# Audio.net
KiCad netlist of a schematic drawn in Altium Designer
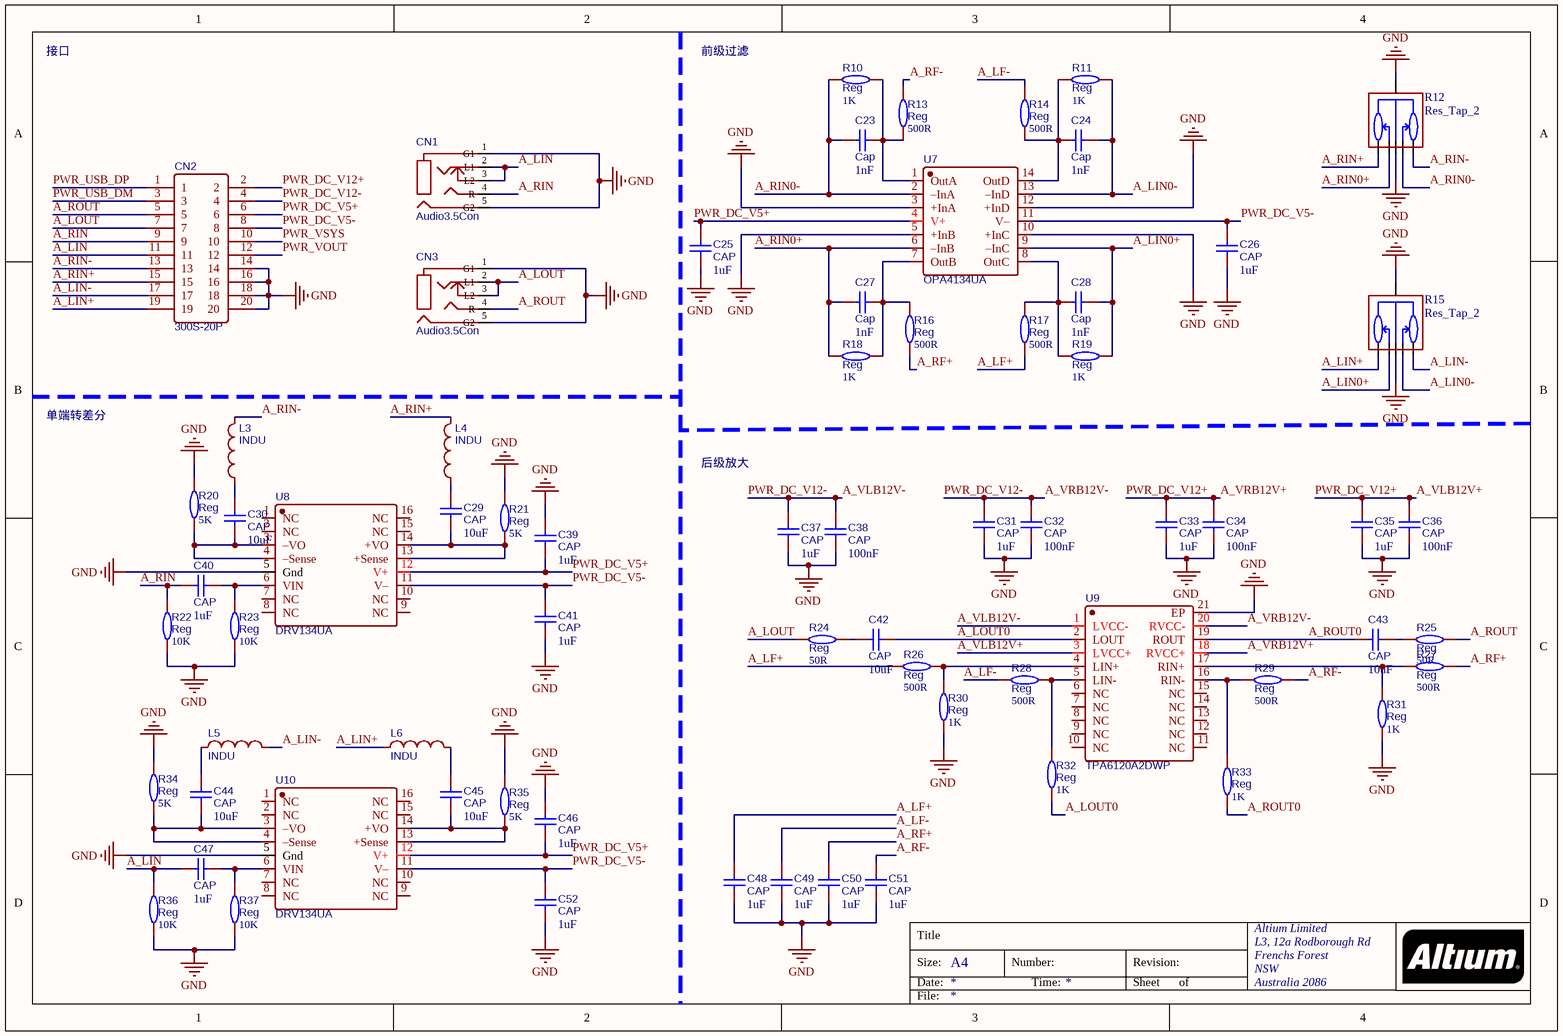
[diagram p0: Audio.SchDoc]

(export (version "E")
  (design (tool "Eeschema 10.0.6"))
  (components
    (comp (ref "C23")
      (value "Cap")
      (footprint "C0603")
      (fields
        (field (name "BOM_SUPPLIER PART") "C302008")
        (field (name "BOM_MANUFACTURER PART") "0603B103K101CT")
        (field (name "ALTIUM_VALUE") "1nF")
        (field (name "CONTRIBUTOR") "LCSC")
      )
      (libsource (lib "Levent_lib") (part "CAP"))
    )
    (comp (ref "C24")
      (value "Cap")
      (footprint "C0603")
      (fields
        (field (name "BOM_SUPPLIER PART") "C302008")
        (field (name "BOM_MANUFACTURER PART") "0603B103K101CT")
        (field (name "ALTIUM_VALUE") "1nF")
        (field (name "CONTRIBUTOR") "LCSC")
      )
      (libsource (lib "Levent_lib") (part "CAP"))
    )
    (comp (ref "C25")
      (value "CAP")
      (footprint "C0603")
      (description "Cap")
      (fields
        (field (name "BOM_SUPPLIER PART") "C302008")
        (field (name "BOM_MANUFACTURER PART") "0603B103K101CT")
        (field (name "ALTIUM_VALUE") "1uF")
        (field (name "CONTRIBUTOR") "LCSC")
      )
      (libsource (lib "Levent_lib") (part "CAP"))
    )
    (comp (ref "C26")
      (value "CAP")
      (footprint "C0603")
      (description "Cap")
      (fields
        (field (name "BOM_SUPPLIER PART") "C302008")
        (field (name "BOM_MANUFACTURER PART") "0603B103K101CT")
        (field (name "ALTIUM_VALUE") "1uF")
        (field (name "CONTRIBUTOR") "LCSC")
      )
      (libsource (lib "Levent_lib") (part "CAP"))
    )
    (comp (ref "C27")
      (value "Cap")
      (footprint "C0603")
      (fields
        (field (name "BOM_SUPPLIER PART") "C302008")
        (field (name "BOM_MANUFACTURER PART") "0603B103K101CT")
        (field (name "ALTIUM_VALUE") "1nF")
        (field (name "CONTRIBUTOR") "LCSC")
      )
      (libsource (lib "Levent_lib") (part "CAP"))
    )
    (comp (ref "C28")
      (value "Cap")
      (footprint "C0603")
      (fields
        (field (name "BOM_SUPPLIER PART") "C302008")
        (field (name "BOM_MANUFACTURER PART") "0603B103K101CT")
        (field (name "ALTIUM_VALUE") "1nF")
        (field (name "CONTRIBUTOR") "LCSC")
      )
      (libsource (lib "Levent_lib") (part "CAP"))
    )
    (comp (ref "C29")
      (value "CAP")
      (footprint "C0603")
      (description "Cap")
      (fields
        (field (name "BOM_SUPPLIER PART") "C302008")
        (field (name "BOM_MANUFACTURER PART") "0603B103K101CT")
        (field (name "ALTIUM_VALUE") "10uF")
        (field (name "CONTRIBUTOR") "LCSC")
      )
      (libsource (lib "Levent_lib") (part "CAP"))
    )
    (comp (ref "C30")
      (value "CAP")
      (footprint "C0603")
      (description "Cap")
      (fields
        (field (name "BOM_SUPPLIER PART") "C302008")
        (field (name "BOM_MANUFACTURER PART") "0603B103K101CT")
        (field (name "ALTIUM_VALUE") "10uF")
        (field (name "CONTRIBUTOR") "LCSC")
      )
      (libsource (lib "Levent_lib") (part "CAP"))
    )
    (comp (ref "C31")
      (value "CAP")
      (footprint "C0603")
      (description "Cap")
      (fields
        (field (name "BOM_SUPPLIER PART") "C302008")
        (field (name "BOM_MANUFACTURER PART") "0603B103K101CT")
        (field (name "ALTIUM_VALUE") "1uF")
        (field (name "CONTRIBUTOR") "LCSC")
      )
      (libsource (lib "Levent_lib") (part "CAP"))
    )
    (comp (ref "C32")
      (value "CAP")
      (footprint "C0603")
      (description "Cap")
      (fields
        (field (name "BOM_SUPPLIER PART") "C302008")
        (field (name "BOM_MANUFACTURER PART") "0603B103K101CT")
        (field (name "ALTIUM_VALUE") "100nF")
        (field (name "CONTRIBUTOR") "LCSC")
      )
      (libsource (lib "Levent_lib") (part "CAP"))
    )
    (comp (ref "C33")
      (value "CAP")
      (footprint "C0603")
      (description "Cap")
      (fields
        (field (name "BOM_SUPPLIER PART") "C302008")
        (field (name "BOM_MANUFACTURER PART") "0603B103K101CT")
        (field (name "ALTIUM_VALUE") "1uF")
        (field (name "CONTRIBUTOR") "LCSC")
      )
      (libsource (lib "Levent_lib") (part "CAP"))
    )
    (comp (ref "C34")
      (value "CAP")
      (footprint "C0603")
      (description "Cap")
      (fields
        (field (name "BOM_SUPPLIER PART") "C302008")
        (field (name "BOM_MANUFACTURER PART") "0603B103K101CT")
        (field (name "ALTIUM_VALUE") "100nF")
        (field (name "CONTRIBUTOR") "LCSC")
      )
      (libsource (lib "Levent_lib") (part "CAP"))
    )
    (comp (ref "C35")
      (value "CAP")
      (footprint "C0603")
      (description "Cap")
      (fields
        (field (name "BOM_SUPPLIER PART") "C302008")
        (field (name "BOM_MANUFACTURER PART") "0603B103K101CT")
        (field (name "ALTIUM_VALUE") "1uF")
        (field (name "CONTRIBUTOR") "LCSC")
      )
      (libsource (lib "Levent_lib") (part "CAP"))
    )
    (comp (ref "C36")
      (value "CAP")
      (footprint "C0603")
      (description "Cap")
      (fields
        (field (name "BOM_SUPPLIER PART") "C302008")
        (field (name "BOM_MANUFACTURER PART") "0603B103K101CT")
        (field (name "ALTIUM_VALUE") "100nF")
        (field (name "CONTRIBUTOR") "LCSC")
      )
      (libsource (lib "Levent_lib") (part "CAP"))
    )
    (comp (ref "C37")
      (value "CAP")
      (footprint "C0603")
      (description "Cap")
      (fields
        (field (name "BOM_SUPPLIER PART") "C302008")
        (field (name "BOM_MANUFACTURER PART") "0603B103K101CT")
        (field (name "ALTIUM_VALUE") "1uF")
        (field (name "CONTRIBUTOR") "LCSC")
      )
      (libsource (lib "Levent_lib") (part "CAP"))
    )
    (comp (ref "C38")
      (value "CAP")
      (footprint "C0603")
      (description "Cap")
      (fields
        (field (name "BOM_SUPPLIER PART") "C302008")
        (field (name "BOM_MANUFACTURER PART") "0603B103K101CT")
        (field (name "ALTIUM_VALUE") "100nF")
        (field (name "CONTRIBUTOR") "LCSC")
      )
      (libsource (lib "Levent_lib") (part "CAP"))
    )
    (comp (ref "C39")
      (value "CAP")
      (footprint "C0603")
      (description "Cap")
      (fields
        (field (name "BOM_SUPPLIER PART") "C302008")
        (field (name "BOM_MANUFACTURER PART") "0603B103K101CT")
        (field (name "ALTIUM_VALUE") "1uF")
        (field (name "CONTRIBUTOR") "LCSC")
      )
      (libsource (lib "Levent_lib") (part "CAP"))
    )
    (comp (ref "C40")
      (value "CAP")
      (footprint "C0603")
      (description "Cap")
      (fields
        (field (name "BOM_SUPPLIER PART") "C302008")
        (field (name "BOM_MANUFACTURER PART") "0603B103K101CT")
        (field (name "ALTIUM_VALUE") "1uF")
        (field (name "CONTRIBUTOR") "LCSC")
      )
      (libsource (lib "Levent_lib") (part "CAP"))
    )
    (comp (ref "C41")
      (value "CAP")
      (footprint "C0603")
      (description "Cap")
      (fields
        (field (name "BOM_SUPPLIER PART") "C302008")
        (field (name "BOM_MANUFACTURER PART") "0603B103K101CT")
        (field (name "ALTIUM_VALUE") "1uF")
        (field (name "CONTRIBUTOR") "LCSC")
      )
      (libsource (lib "Levent_lib") (part "CAP"))
    )
    (comp (ref "C42")
      (value "CAP")
      (footprint "C0603")
      (description "Cap")
      (fields
        (field (name "BOM_SUPPLIER PART") "C302008")
        (field (name "BOM_MANUFACTURER PART") "0603B103K101CT")
        (field (name "ALTIUM_VALUE") "10uF")
        (field (name "CONTRIBUTOR") "LCSC")
      )
      (libsource (lib "Levent_lib") (part "CAP"))
    )
    (comp (ref "C43")
      (value "CAP")
      (footprint "C0603")
      (description "Cap")
      (fields
        (field (name "BOM_SUPPLIER PART") "C302008")
        (field (name "BOM_MANUFACTURER PART") "0603B103K101CT")
        (field (name "ALTIUM_VALUE") "10uF")
        (field (name "CONTRIBUTOR") "LCSC")
      )
      (libsource (lib "Levent_lib") (part "CAP"))
    )
    (comp (ref "C44")
      (value "CAP")
      (footprint "C0603")
      (description "Cap")
      (fields
        (field (name "BOM_SUPPLIER PART") "C302008")
        (field (name "BOM_MANUFACTURER PART") "0603B103K101CT")
        (field (name "ALTIUM_VALUE") "10uF")
        (field (name "CONTRIBUTOR") "LCSC")
      )
      (libsource (lib "Levent_lib") (part "CAP"))
    )
    (comp (ref "C45")
      (value "CAP")
      (footprint "C0603")
      (description "Cap")
      (fields
        (field (name "BOM_SUPPLIER PART") "C302008")
        (field (name "BOM_MANUFACTURER PART") "0603B103K101CT")
        (field (name "ALTIUM_VALUE") "10uF")
        (field (name "CONTRIBUTOR") "LCSC")
      )
      (libsource (lib "Levent_lib") (part "CAP"))
    )
    (comp (ref "C46")
      (value "CAP")
      (footprint "C0603")
      (description "Cap")
      (fields
        (field (name "BOM_SUPPLIER PART") "C302008")
        (field (name "BOM_MANUFACTURER PART") "0603B103K101CT")
        (field (name "ALTIUM_VALUE") "1uF")
        (field (name "CONTRIBUTOR") "LCSC")
      )
      (libsource (lib "Levent_lib") (part "CAP"))
    )
    (comp (ref "C47")
      (value "CAP")
      (footprint "C0603")
      (description "Cap")
      (fields
        (field (name "BOM_SUPPLIER PART") "C302008")
        (field (name "BOM_MANUFACTURER PART") "0603B103K101CT")
        (field (name "ALTIUM_VALUE") "1uF")
        (field (name "CONTRIBUTOR") "LCSC")
      )
      (libsource (lib "Levent_lib") (part "CAP"))
    )
    (comp (ref "C48")
      (value "CAP")
      (footprint "C0603")
      (description "Cap")
      (fields
        (field (name "BOM_SUPPLIER PART") "C302008")
        (field (name "BOM_MANUFACTURER PART") "0603B103K101CT")
        (field (name "ALTIUM_VALUE") "1uF")
        (field (name "CONTRIBUTOR") "LCSC")
      )
      (libsource (lib "Levent_lib") (part "CAP"))
    )
    (comp (ref "C49")
      (value "CAP")
      (footprint "C0603")
      (description "Cap")
      (fields
        (field (name "BOM_SUPPLIER PART") "C302008")
        (field (name "BOM_MANUFACTURER PART") "0603B103K101CT")
        (field (name "ALTIUM_VALUE") "1uF")
        (field (name "CONTRIBUTOR") "LCSC")
      )
      (libsource (lib "Levent_lib") (part "CAP"))
    )
    (comp (ref "C50")
      (value "CAP")
      (footprint "C0603")
      (description "Cap")
      (fields
        (field (name "BOM_SUPPLIER PART") "C302008")
        (field (name "BOM_MANUFACTURER PART") "0603B103K101CT")
        (field (name "ALTIUM_VALUE") "1uF")
        (field (name "CONTRIBUTOR") "LCSC")
      )
      (libsource (lib "Levent_lib") (part "CAP"))
    )
    (comp (ref "C51")
      (value "CAP")
      (footprint "C0603")
      (description "Cap")
      (fields
        (field (name "BOM_SUPPLIER PART") "C302008")
        (field (name "BOM_MANUFACTURER PART") "0603B103K101CT")
        (field (name "ALTIUM_VALUE") "1uF")
        (field (name "CONTRIBUTOR") "LCSC")
      )
      (libsource (lib "Levent_lib") (part "CAP"))
    )
    (comp (ref "C52")
      (value "CAP")
      (footprint "C0603")
      (description "Cap")
      (fields
        (field (name "BOM_SUPPLIER PART") "C302008")
        (field (name "BOM_MANUFACTURER PART") "0603B103K101CT")
        (field (name "ALTIUM_VALUE") "1uF")
        (field (name "CONTRIBUTOR") "LCSC")
      )
      (libsource (lib "Levent_lib") (part "CAP"))
    )
    (comp (ref "CN1")
      (value "Audio3.5Con")
      (footprint "Audio3.5_3Pin")
      (description "3.5mm 3Pin 音频接口")
      (fields
        (field (name "BOM_SUPPLIER PART") "C2837065")
        (field (name "BOM_MANUFACTURER PART") "PJ-393")
        (field (name "CONTRIBUTOR") "LCSC")
      )
      (libsource (lib "Levent_lib") (part "AudioCon3"))
    )
    (comp (ref "CN2")
      (value "300S-20P")
      (footprint "DC_20P_2.54")
      (description "DC牛角座，20P")
      (fields (field (name "BOM_SUPPLIER PART") "C132442") (field (name "CONTRIBUTOR") "LCSC"))
      (libsource (lib "Levent_lib") (part "DC-20P"))
    )
    (comp (ref "CN3")
      (value "Audio3.5Con")
      (footprint "Audio3.5_3Pin")
      (description "3.5mm 3Pin 音频接口")
      (fields
        (field (name "BOM_SUPPLIER PART") "C2837065")
        (field (name "BOM_MANUFACTURER PART") "PJ-393")
        (field (name "CONTRIBUTOR") "LCSC")
      )
      (libsource (lib "Levent_lib") (part "AudioCon3"))
    )
    (comp (ref "L3")
      (value "INDU")
      (footprint "L1210")
      (description "电感")
      (fields
        (field (name "BOM_SUPPLIER PART") "C182182")
        (field (name "BOM_MANUFACTURER PART") "SLO0630H150MTT")
        (field (name "CONTRIBUTOR") "LCSC")
      )
      (libsource (lib "Levent_lib") (part "IND"))
    )
    (comp (ref "L4")
      (value "INDU")
      (footprint "L1210")
      (description "电感")
      (fields
        (field (name "BOM_SUPPLIER PART") "C182182")
        (field (name "BOM_MANUFACTURER PART") "SLO0630H150MTT")
        (field (name "CONTRIBUTOR") "LCSC")
      )
      (libsource (lib "Levent_lib") (part "IND"))
    )
    (comp (ref "L5")
      (value "INDU")
      (footprint "L1210")
      (description "电感")
      (fields
        (field (name "BOM_SUPPLIER PART") "C182182")
        (field (name "BOM_MANUFACTURER PART") "SLO0630H150MTT")
        (field (name "CONTRIBUTOR") "LCSC")
      )
      (libsource (lib "Levent_lib") (part "IND"))
    )
    (comp (ref "L6")
      (value "INDU")
      (footprint "L1210")
      (description "电感")
      (fields
        (field (name "BOM_SUPPLIER PART") "C182182")
        (field (name "BOM_MANUFACTURER PART") "SLO0630H150MTT")
        (field (name "CONTRIBUTOR") "LCSC")
      )
      (libsource (lib "Levent_lib") (part "IND"))
    )
    (comp (ref "R10")
      (value "Reg")
      (footprint "R0603")
      (description "电阻")
      (fields
        (field (name "BOM_SUPPLIER PART") "C465721")
        (field (name "BOM_MANUFACTURER PART") "AR03BTCX1002A")
        (field (name "ALTIUM_VALUE") "1K")
        (field (name "CONTRIBUTOR") "LCSC")
      )
      (libsource (lib "Levent_lib") (part "Res"))
    )
    (comp (ref "R11")
      (value "Reg")
      (footprint "R0603")
      (description "电阻")
      (fields
        (field (name "BOM_SUPPLIER PART") "C465721")
        (field (name "BOM_MANUFACTURER PART") "AR03BTCX1002A")
        (field (name "ALTIUM_VALUE") "1K")
        (field (name "CONTRIBUTOR") "LCSC")
      )
      (libsource (lib "Levent_lib") (part "Res"))
    )
    (comp (ref "R12")
      (value "Res_Tap_2")
      (footprint "RES_TAP_5Pin")
      (description "双联电位器")
      (libsource (lib "Levent_lib") (part "Res_Tap_2"))
    )
    (comp (ref "R13")
      (value "Reg")
      (footprint "R0603")
      (description "电阻")
      (fields
        (field (name "BOM_SUPPLIER PART") "C465721")
        (field (name "BOM_MANUFACTURER PART") "AR03BTCX1002A")
        (field (name "ALTIUM_VALUE") "500R")
        (field (name "CONTRIBUTOR") "LCSC")
      )
      (libsource (lib "Levent_lib") (part "Res"))
    )
    (comp (ref "R14")
      (value "Reg")
      (footprint "R0603")
      (description "电阻")
      (fields
        (field (name "BOM_SUPPLIER PART") "C465721")
        (field (name "BOM_MANUFACTURER PART") "AR03BTCX1002A")
        (field (name "ALTIUM_VALUE") "500R")
        (field (name "CONTRIBUTOR") "LCSC")
      )
      (libsource (lib "Levent_lib") (part "Res"))
    )
    (comp (ref "R15")
      (value "Res_Tap_2")
      (footprint "RES_TAP_5Pin")
      (description "双联电位器")
      (libsource (lib "Levent_lib") (part "Res_Tap_2"))
    )
    (comp (ref "R16")
      (value "Reg")
      (footprint "R0603")
      (description "电阻")
      (fields
        (field (name "BOM_SUPPLIER PART") "C465721")
        (field (name "BOM_MANUFACTURER PART") "AR03BTCX1002A")
        (field (name "ALTIUM_VALUE") "500R")
        (field (name "CONTRIBUTOR") "LCSC")
      )
      (libsource (lib "Levent_lib") (part "Res"))
    )
    (comp (ref "R17")
      (value "Reg")
      (footprint "R0603")
      (description "电阻")
      (fields
        (field (name "BOM_SUPPLIER PART") "C465721")
        (field (name "BOM_MANUFACTURER PART") "AR03BTCX1002A")
        (field (name "ALTIUM_VALUE") "500R")
        (field (name "CONTRIBUTOR") "LCSC")
      )
      (libsource (lib "Levent_lib") (part "Res"))
    )
    (comp (ref "R18")
      (value "Reg")
      (footprint "R0603")
      (description "电阻")
      (fields
        (field (name "BOM_SUPPLIER PART") "C465721")
        (field (name "BOM_MANUFACTURER PART") "AR03BTCX1002A")
        (field (name "ALTIUM_VALUE") "1K")
        (field (name "CONTRIBUTOR") "LCSC")
      )
      (libsource (lib "Levent_lib") (part "Res"))
    )
    (comp (ref "R19")
      (value "Reg")
      (footprint "R0603")
      (description "电阻")
      (fields
        (field (name "BOM_SUPPLIER PART") "C465721")
        (field (name "BOM_MANUFACTURER PART") "AR03BTCX1002A")
        (field (name "ALTIUM_VALUE") "1K")
        (field (name "CONTRIBUTOR") "LCSC")
      )
      (libsource (lib "Levent_lib") (part "Res"))
    )
    (comp (ref "R20")
      (value "Reg")
      (footprint "R0603")
      (description "电阻")
      (fields
        (field (name "BOM_SUPPLIER PART") "C465721")
        (field (name "BOM_MANUFACTURER PART") "AR03BTCX1002A")
        (field (name "ALTIUM_VALUE") "5K")
        (field (name "CONTRIBUTOR") "LCSC")
      )
      (libsource (lib "Levent_lib") (part "Res"))
    )
    (comp (ref "R21")
      (value "Reg")
      (footprint "R0603")
      (description "电阻")
      (fields
        (field (name "BOM_SUPPLIER PART") "C465721")
        (field (name "BOM_MANUFACTURER PART") "AR03BTCX1002A")
        (field (name "ALTIUM_VALUE") "5K")
        (field (name "CONTRIBUTOR") "LCSC")
      )
      (libsource (lib "Levent_lib") (part "Res"))
    )
    (comp (ref "R22")
      (value "Reg")
      (footprint "R0603")
      (description "电阻")
      (fields
        (field (name "BOM_SUPPLIER PART") "C465721")
        (field (name "BOM_MANUFACTURER PART") "AR03BTCX1002A")
        (field (name "ALTIUM_VALUE") "10K")
        (field (name "CONTRIBUTOR") "LCSC")
      )
      (libsource (lib "Levent_lib") (part "Res"))
    )
    (comp (ref "R23")
      (value "Reg")
      (footprint "R0603")
      (description "电阻")
      (fields
        (field (name "BOM_SUPPLIER PART") "C465721")
        (field (name "BOM_MANUFACTURER PART") "AR03BTCX1002A")
        (field (name "ALTIUM_VALUE") "10K")
        (field (name "CONTRIBUTOR") "LCSC")
      )
      (libsource (lib "Levent_lib") (part "Res"))
    )
    (comp (ref "R24")
      (value "Reg")
      (footprint "R0603")
      (description "电阻")
      (fields
        (field (name "BOM_SUPPLIER PART") "C465721")
        (field (name "BOM_MANUFACTURER PART") "AR03BTCX1002A")
        (field (name "ALTIUM_VALUE") "50R")
        (field (name "CONTRIBUTOR") "LCSC")
      )
      (libsource (lib "Levent_lib") (part "Res"))
    )
    (comp (ref "R25")
      (value "Reg")
      (footprint "R0603")
      (description "电阻")
      (fields
        (field (name "BOM_SUPPLIER PART") "C465721")
        (field (name "BOM_MANUFACTURER PART") "AR03BTCX1002A")
        (field (name "ALTIUM_VALUE") "50R")
        (field (name "CONTRIBUTOR") "LCSC")
      )
      (libsource (lib "Levent_lib") (part "Res"))
    )
    (comp (ref "R26")
      (value "Reg")
      (footprint "R0603")
      (description "电阻")
      (fields
        (field (name "BOM_SUPPLIER PART") "C465721")
        (field (name "BOM_MANUFACTURER PART") "AR03BTCX1002A")
        (field (name "ALTIUM_VALUE") "500R")
        (field (name "CONTRIBUTOR") "LCSC")
      )
      (libsource (lib "Levent_lib") (part "Res"))
    )
    (comp (ref "R27")
      (value "Reg")
      (footprint "R0603")
      (description "电阻")
      (fields
        (field (name "BOM_SUPPLIER PART") "C465721")
        (field (name "BOM_MANUFACTURER PART") "AR03BTCX1002A")
        (field (name "ALTIUM_VALUE") "500R")
        (field (name "CONTRIBUTOR") "LCSC")
      )
      (libsource (lib "Levent_lib") (part "Res"))
    )
    (comp (ref "R28")
      (value "Reg")
      (footprint "R0603")
      (description "电阻")
      (fields
        (field (name "BOM_SUPPLIER PART") "C465721")
        (field (name "BOM_MANUFACTURER PART") "AR03BTCX1002A")
        (field (name "ALTIUM_VALUE") "500R")
        (field (name "CONTRIBUTOR") "LCSC")
      )
      (libsource (lib "Levent_lib") (part "Res"))
    )
    (comp (ref "R29")
      (value "Reg")
      (footprint "R0603")
      (description "电阻")
      (fields
        (field (name "BOM_SUPPLIER PART") "C465721")
        (field (name "BOM_MANUFACTURER PART") "AR03BTCX1002A")
        (field (name "ALTIUM_VALUE") "500R")
        (field (name "CONTRIBUTOR") "LCSC")
      )
      (libsource (lib "Levent_lib") (part "Res"))
    )
    (comp (ref "R30")
      (value "Reg")
      (footprint "R0603")
      (description "电阻")
      (fields
        (field (name "BOM_SUPPLIER PART") "C465721")
        (field (name "BOM_MANUFACTURER PART") "AR03BTCX1002A")
        (field (name "ALTIUM_VALUE") "1K")
        (field (name "CONTRIBUTOR") "LCSC")
      )
      (libsource (lib "Levent_lib") (part "Res"))
    )
    (comp (ref "R31")
      (value "Reg")
      (footprint "R0603")
      (description "电阻")
      (fields
        (field (name "BOM_SUPPLIER PART") "C465721")
        (field (name "BOM_MANUFACTURER PART") "AR03BTCX1002A")
        (field (name "ALTIUM_VALUE") "1K")
        (field (name "CONTRIBUTOR") "LCSC")
      )
      (libsource (lib "Levent_lib") (part "Res"))
    )
    (comp (ref "R32")
      (value "Reg")
      (footprint "R0603")
      (description "电阻")
      (fields
        (field (name "BOM_SUPPLIER PART") "C465721")
        (field (name "BOM_MANUFACTURER PART") "AR03BTCX1002A")
        (field (name "ALTIUM_VALUE") "1K")
        (field (name "CONTRIBUTOR") "LCSC")
      )
      (libsource (lib "Levent_lib") (part "Res"))
    )
    (comp (ref "R33")
      (value "Reg")
      (footprint "R0603")
      (description "电阻")
      (fields
        (field (name "BOM_SUPPLIER PART") "C465721")
        (field (name "BOM_MANUFACTURER PART") "AR03BTCX1002A")
        (field (name "ALTIUM_VALUE") "1K")
        (field (name "CONTRIBUTOR") "LCSC")
      )
      (libsource (lib "Levent_lib") (part "Res"))
    )
    (comp (ref "R34")
      (value "Reg")
      (footprint "R0603")
      (description "电阻")
      (fields
        (field (name "BOM_SUPPLIER PART") "C465721")
        (field (name "BOM_MANUFACTURER PART") "AR03BTCX1002A")
        (field (name "ALTIUM_VALUE") "5K")
        (field (name "CONTRIBUTOR") "LCSC")
      )
      (libsource (lib "Levent_lib") (part "Res"))
    )
    (comp (ref "R35")
      (value "Reg")
      (footprint "R0603")
      (description "电阻")
      (fields
        (field (name "BOM_SUPPLIER PART") "C465721")
        (field (name "BOM_MANUFACTURER PART") "AR03BTCX1002A")
        (field (name "ALTIUM_VALUE") "5K")
        (field (name "CONTRIBUTOR") "LCSC")
      )
      (libsource (lib "Levent_lib") (part "Res"))
    )
    (comp (ref "R36")
      (value "Reg")
      (footprint "R0603")
      (description "电阻")
      (fields
        (field (name "BOM_SUPPLIER PART") "C465721")
        (field (name "BOM_MANUFACTURER PART") "AR03BTCX1002A")
        (field (name "ALTIUM_VALUE") "10K")
        (field (name "CONTRIBUTOR") "LCSC")
      )
      (libsource (lib "Levent_lib") (part "Res"))
    )
    (comp (ref "R37")
      (value "Reg")
      (footprint "R0603")
      (description "电阻")
      (fields
        (field (name "BOM_SUPPLIER PART") "C465721")
        (field (name "BOM_MANUFACTURER PART") "AR03BTCX1002A")
        (field (name "ALTIUM_VALUE") "10K")
        (field (name "CONTRIBUTOR") "LCSC")
      )
      (libsource (lib "Levent_lib") (part "Res"))
    )
    (comp (ref "U7")
      (value "OPA4134UA")
      (footprint "SOIC-14")
      (description "耳放")
      (fields (field (name "BOM_SUPPLIER PART") "C2832240") (field (name "CONTRIBUTOR") "LCSC"))
      (libsource (lib "Levent_lib") (part "OPA4134UA"))
    )
    (comp (ref "U8")
      (value "DRV134UA")
      (footprint "SOIC-16_9.5mm")
      (description "音频差分放大器")
      (fields (field (name "BOM_SUPPLIER PART") "C1519988") (field (name "CONTRIBUTOR") "LCSC"))
      (libsource (lib "Levent_lib") (part "DRV134UA"))
    )
    (comp (ref "U9")
      (value "TPA6120A2DWP")
      (footprint "HSOP-20")
      (description "耳放")
      (fields (field (name "BOM_SUPPLIER PART") "C2871054") (field (name "CONTRIBUTOR") "LCSC"))
      (libsource (lib "Levent_lib") (part "TPA6120"))
    )
    (comp (ref "U10")
      (value "DRV134UA")
      (footprint "SOIC-16_9.5mm")
      (description "音频差分放大器")
      (fields (field (name "BOM_SUPPLIER PART") "C1519988") (field (name "CONTRIBUTOR") "LCSC"))
      (libsource (lib "Levent_lib") (part "DRV134UA"))
    )
  )
  (nets
    (net (code "1") (name "/A_LF+") (class "Default")
      (node (ref "C48") (pin "1") (pinfunction "1_1") (pintype "passive"))
      (node (ref "R17") (pin "1") (pinfunction "1_1") (pintype "passive"))
      (node (ref "R26") (pin "1") (pinfunction "1_1") (pintype "passive"))
    )
    (net (code "2") (name "/A_LF-") (class "Default")
      (node (ref "C49") (pin "1") (pinfunction "1_1") (pintype "passive"))
      (node (ref "R14") (pin "2") (pinfunction "2_2") (pintype "passive"))
      (node (ref "R28") (pin "1") (pinfunction "1_1") (pintype "passive"))
    )
    (net (code "3") (name "/A_LIN") (class "Default")
      (node (ref "C47") (pin "1") (pinfunction "1_1") (pintype "passive"))
      (node (ref "CN1") (pin "2") (pinfunction "L1_2") (pintype "passive"))
      (node (ref "CN1") (pin "3") (pinfunction "L2_3") (pintype "passive"))
      (node (ref "CN2") (pin "11") (pinfunction "11_11") (pintype "passive"))
      (node (ref "R36") (pin "2") (pinfunction "2_2") (pintype "passive"))
    )
    (net (code "4") (name "/A_LIN+") (class "Default")
      (node (ref "CN2") (pin "19") (pinfunction "19_19") (pintype "passive"))
      (node (ref "L6") (pin "1") (pinfunction "1_1") (pintype "passive"))
      (node (ref "R15") (pin "4") (pinfunction "CH2B_4") (pintype "passive"))
    )
    (net (code "5") (name "/A_LIN-") (class "Default")
      (node (ref "CN2") (pin "17") (pinfunction "17_17") (pintype "passive"))
      (node (ref "L5") (pin "2") (pinfunction "2_2") (pintype "passive"))
      (node (ref "R15") (pin "5") (pinfunction "CH1B_5") (pintype "passive"))
    )
    (net (code "6") (name "/A_LIN0+") (class "Default")
      (node (ref "C28") (pin "2") (pinfunction "2_2") (pintype "passive"))
      (node (ref "R15") (pin "3") (pinfunction "CH2A_3") (pintype "passive"))
      (node (ref "R19") (pin "2") (pinfunction "2_2") (pintype "passive"))
      (node (ref "U7") (pin "9") (pinfunction "–InC_9") (pintype "passive"))
    )
    (net (code "7") (name "/A_LIN0-") (class "Default")
      (node (ref "C24") (pin "2") (pinfunction "2_2") (pintype "passive"))
      (node (ref "R11") (pin "2") (pinfunction "2_2") (pintype "passive"))
      (node (ref "R15") (pin "2") (pinfunction "CH1A_2") (pintype "passive"))
      (node (ref "U7") (pin "13") (pinfunction "–InD_13") (pintype "passive"))
    )
    (net (code "8") (name "/A_LOUT") (class "Default")
      (node (ref "CN2") (pin "7") (pinfunction "7_7") (pintype "passive"))
      (node (ref "CN3") (pin "2") (pinfunction "L1_2") (pintype "passive"))
      (node (ref "CN3") (pin "3") (pinfunction "L2_3") (pintype "passive"))
      (node (ref "R24") (pin "1") (pinfunction "1_1") (pintype "passive"))
    )
    (net (code "9") (name "/A_LOUT0") (class "Default")
      (node (ref "C42") (pin "1") (pinfunction "1_1") (pintype "passive"))
      (node (ref "R32") (pin "1") (pinfunction "1_1") (pintype "passive"))
      (node (ref "U9") (pin "2") (pinfunction "LOUT_2") (pintype "passive"))
    )
    (net (code "10") (name "/A_RF+") (class "Default")
      (node (ref "C50") (pin "1") (pinfunction "1_1") (pintype "passive"))
      (node (ref "R16") (pin "1") (pinfunction "1_1") (pintype "passive"))
      (node (ref "R27") (pin "1") (pinfunction "1_1") (pintype "passive"))
    )
    (net (code "11") (name "/A_RF-") (class "Default")
      (node (ref "C51") (pin "1") (pinfunction "1_1") (pintype "passive"))
      (node (ref "R13") (pin "2") (pinfunction "2_2") (pintype "passive"))
      (node (ref "R29") (pin "1") (pinfunction "1_1") (pintype "passive"))
    )
    (net (code "12") (name "/A_RIN") (class "Default")
      (node (ref "C40") (pin "1") (pinfunction "1_1") (pintype "passive"))
      (node (ref "CN1") (pin "4") (pinfunction "R_4") (pintype "passive"))
      (node (ref "CN2") (pin "9") (pinfunction "9_9") (pintype "passive"))
      (node (ref "R22") (pin "2") (pinfunction "2_2") (pintype "passive"))
    )
    (net (code "13") (name "/A_RIN+") (class "Default")
      (node (ref "CN2") (pin "15") (pinfunction "15_15") (pintype "passive"))
      (node (ref "L4") (pin "2") (pinfunction "2_2") (pintype "passive"))
      (node (ref "R12") (pin "4") (pinfunction "CH2B_4") (pintype "passive"))
    )
    (net (code "14") (name "/A_RIN-") (class "Default")
      (node (ref "CN2") (pin "13") (pinfunction "13_13") (pintype "passive"))
      (node (ref "L3") (pin "2") (pinfunction "2_2") (pintype "passive"))
      (node (ref "R12") (pin "5") (pinfunction "CH1B_5") (pintype "passive"))
    )
    (net (code "15") (name "/A_RIN0+") (class "Default")
      (node (ref "C27") (pin "1") (pinfunction "1_1") (pintype "passive"))
      (node (ref "R12") (pin "3") (pinfunction "CH2A_3") (pintype "passive"))
      (node (ref "R18") (pin "1") (pinfunction "1_1") (pintype "passive"))
      (node (ref "U7") (pin "6") (pinfunction "–InB_6") (pintype "passive"))
    )
    (net (code "16") (name "/A_RIN0-") (class "Default")
      (node (ref "C23") (pin "1") (pinfunction "1_1") (pintype "passive"))
      (node (ref "R10") (pin "1") (pinfunction "1_1") (pintype "passive"))
      (node (ref "R12") (pin "2") (pinfunction "CH1A_2") (pintype "passive"))
      (node (ref "U7") (pin "2") (pinfunction "–InA_2") (pintype "passive"))
    )
    (net (code "17") (name "/A_ROUT") (class "Default")
      (node (ref "CN2") (pin "5") (pinfunction "5_5") (pintype "passive"))
      (node (ref "CN3") (pin "4") (pinfunction "R_4") (pintype "passive"))
      (node (ref "R25") (pin "2") (pinfunction "2_2") (pintype "passive"))
    )
    (net (code "18") (name "/A_ROUT0") (class "Default")
      (node (ref "C43") (pin "2") (pinfunction "2_2") (pintype "passive"))
      (node (ref "R33") (pin "1") (pinfunction "1_1") (pintype "passive"))
      (node (ref "U9") (pin "19") (pinfunction "ROUT_19") (pintype "passive"))
    )
    (net (code "19") (name "/A_VLB12V+") (class "Default")
      (node (ref "C33") (pin "2") (pinfunction "2_2") (pintype "passive"))
      (node (ref "C34") (pin "2") (pinfunction "2_2") (pintype "passive"))
      (node (ref "C35") (pin "2") (pinfunction "2_2") (pintype "passive"))
      (node (ref "C36") (pin "2") (pinfunction "2_2") (pintype "passive"))
      (node (ref "CN2") (pin "2") (pinfunction "2_2") (pintype "passive"))
      (node (ref "U9") (pin "18") (pinfunction "RVCC+_18") (pintype "passive"))
      (node (ref "U9") (pin "3") (pinfunction "LVCC+_3") (pintype "passive"))
    )
    (net (code "20") (name "/A_VLB12V-") (class "Default")
      (node (ref "C31") (pin "2") (pinfunction "2_2") (pintype "passive"))
      (node (ref "C32") (pin "2") (pinfunction "2_2") (pintype "passive"))
      (node (ref "C37") (pin "2") (pinfunction "2_2") (pintype "passive"))
      (node (ref "C38") (pin "2") (pinfunction "2_2") (pintype "passive"))
      (node (ref "CN2") (pin "4") (pinfunction "4_4") (pintype "passive"))
      (node (ref "U9") (pin "1") (pinfunction "LVCC-_1") (pintype "passive"))
      (node (ref "U9") (pin "20") (pinfunction "RVCC-_20") (pintype "passive"))
    )
    (net (code "21") (name "/PWR_DC_V5+") (class "Default")
      (node (ref "C25") (pin "2") (pinfunction "2_2") (pintype "passive"))
      (node (ref "C39") (pin "1") (pinfunction "1_1") (pintype "passive"))
      (node (ref "C46") (pin "1") (pinfunction "1_1") (pintype "passive"))
      (node (ref "CN2") (pin "6") (pinfunction "6_6") (pintype "passive"))
      (node (ref "U10") (pin "12") (pinfunction "V+_12") (pintype "passive"))
      (node (ref "U7") (pin "4") (pinfunction "V+_4") (pintype "passive"))
      (node (ref "U8") (pin "12") (pinfunction "V+_12") (pintype "passive"))
    )
    (net (code "22") (name "/PWR_DC_V5-") (class "Default")
      (node (ref "C26") (pin "2") (pinfunction "2_2") (pintype "passive"))
      (node (ref "C41") (pin "2") (pinfunction "2_2") (pintype "passive"))
      (node (ref "C52") (pin "2") (pinfunction "2_2") (pintype "passive"))
      (node (ref "CN2") (pin "8") (pinfunction "8_8") (pintype "passive"))
      (node (ref "U10") (pin "11") (pinfunction "V–_11") (pintype "passive"))
      (node (ref "U7") (pin "11") (pinfunction "V–_11") (pintype "passive"))
      (node (ref "U8") (pin "11") (pinfunction "V–_11") (pintype "passive"))
    )
    (net (code "23") (name "/PWR_USB_DM") (class "Default")
      (node (ref "CN2") (pin "3") (pinfunction "3_3") (pintype "passive"))
    )
    (net (code "24") (name "/PWR_USB_DP") (class "Default")
      (node (ref "CN2") (pin "1") (pinfunction "1_1") (pintype "passive"))
    )
    (net (code "25") (name "/PWR_VOUT") (class "Default")
      (node (ref "CN2") (pin "12") (pinfunction "12_12") (pintype "passive"))
    )
    (net (code "26") (name "/PWR_VSYS") (class "Default")
      (node (ref "CN2") (pin "10") (pinfunction "10_10") (pintype "passive"))
    )
    (net (code "27") (name "GND") (class "Default")
      (node (ref "C25") (pin "1") (pinfunction "1_1") (pintype "passive"))
      (node (ref "C26") (pin "1") (pinfunction "1_1") (pintype "passive"))
      (node (ref "C31") (pin "1") (pinfunction "1_1") (pintype "passive"))
      (node (ref "C32") (pin "1") (pinfunction "1_1") (pintype "passive"))
      (node (ref "C33") (pin "1") (pinfunction "1_1") (pintype "passive"))
      (node (ref "C34") (pin "1") (pinfunction "1_1") (pintype "passive"))
      (node (ref "C35") (pin "1") (pinfunction "1_1") (pintype "passive"))
      (node (ref "C36") (pin "1") (pinfunction "1_1") (pintype "passive"))
      (node (ref "C37") (pin "1") (pinfunction "1_1") (pintype "passive"))
      (node (ref "C38") (pin "1") (pinfunction "1_1") (pintype "passive"))
      (node (ref "C39") (pin "2") (pinfunction "2_2") (pintype "passive"))
      (node (ref "C41") (pin "1") (pinfunction "1_1") (pintype "passive"))
      (node (ref "C46") (pin "2") (pinfunction "2_2") (pintype "passive"))
      (node (ref "C48") (pin "2") (pinfunction "2_2") (pintype "passive"))
      (node (ref "C49") (pin "2") (pinfunction "2_2") (pintype "passive"))
      (node (ref "C50") (pin "2") (pinfunction "2_2") (pintype "passive"))
      (node (ref "C51") (pin "2") (pinfunction "2_2") (pintype "passive"))
      (node (ref "C52") (pin "1") (pinfunction "1_1") (pintype "passive"))
      (node (ref "CN1") (pin "1") (pinfunction "G1_1") (pintype "passive"))
      (node (ref "CN1") (pin "5") (pinfunction "G2_5") (pintype "passive"))
      (node (ref "CN2") (pin "14") (pinfunction "14_14") (pintype "passive"))
      (node (ref "CN2") (pin "16") (pinfunction "16_16") (pintype "passive"))
      (node (ref "CN2") (pin "18") (pinfunction "18_18") (pintype "passive"))
      (node (ref "CN2") (pin "20") (pinfunction "20_20") (pintype "passive"))
      (node (ref "CN3") (pin "1") (pinfunction "G1_1") (pintype "passive"))
      (node (ref "CN3") (pin "5") (pinfunction "G2_5") (pintype "passive"))
      (node (ref "R12") (pin "1") (pinfunction "G_1") (pintype "passive"))
      (node (ref "R12") (pin "6") (pinfunction "PAD_6") (pintype "passive"))
      (node (ref "R15") (pin "1") (pinfunction "G_1") (pintype "passive"))
      (node (ref "R15") (pin "6") (pinfunction "PAD_6") (pintype "passive"))
      (node (ref "R20") (pin "2") (pinfunction "2_2") (pintype "passive"))
      (node (ref "R21") (pin "1") (pinfunction "1_1") (pintype "passive"))
      (node (ref "R22") (pin "1") (pinfunction "1_1") (pintype "passive"))
      (node (ref "R23") (pin "1") (pinfunction "1_1") (pintype "passive"))
      (node (ref "R30") (pin "1") (pinfunction "1_1") (pintype "passive"))
      (node (ref "R31") (pin "1") (pinfunction "1_1") (pintype "passive"))
      (node (ref "R34") (pin "2") (pinfunction "2_2") (pintype "passive"))
      (node (ref "R35") (pin "1") (pinfunction "1_1") (pintype "passive"))
      (node (ref "R36") (pin "1") (pinfunction "1_1") (pintype "passive"))
      (node (ref "R37") (pin "1") (pinfunction "1_1") (pintype "passive"))
      (node (ref "U10") (pin "5") (pinfunction "Gnd_5") (pintype "passive"))
      (node (ref "U7") (pin "10") (pinfunction "+InC_10") (pintype "passive"))
      (node (ref "U7") (pin "12") (pinfunction "+InD_12") (pintype "passive"))
      (node (ref "U7") (pin "3") (pinfunction "+InA_3") (pintype "passive"))
      (node (ref "U7") (pin "5") (pinfunction "+InB_5") (pintype "passive"))
      (node (ref "U8") (pin "5") (pinfunction "Gnd_5") (pintype "passive"))
      (node (ref "U9") (pin "21") (pinfunction "EP_21") (pintype "passive"))
    )
    (net (code "28") (name "Net-(C29-Pad2)") (class "Default")
      (node (ref "C29") (pin "2") (pinfunction "2_2") (pintype "passive"))
      (node (ref "L4") (pin "1") (pinfunction "1_1") (pintype "passive"))
    )
    (net (code "29") (name "Net-(C30-Pad2)") (class "Default")
      (node (ref "C30") (pin "2") (pinfunction "2_2") (pintype "passive"))
      (node (ref "L3") (pin "1") (pinfunction "1_1") (pintype "passive"))
    )
    (net (code "30") (name "Net-(C42-Pad2)") (class "Default")
      (node (ref "C42") (pin "2") (pinfunction "2_2") (pintype "passive"))
      (node (ref "R24") (pin "2") (pinfunction "2_2") (pintype "passive"))
    )
    (net (code "31") (name "Net-(C43-Pad1)") (class "Default")
      (node (ref "C43") (pin "1") (pinfunction "1_1") (pintype "passive"))
      (node (ref "R25") (pin "1") (pinfunction "1_1") (pintype "passive"))
    )
    (net (code "32") (name "Net-(C44-Pad2)") (class "Default")
      (node (ref "C44") (pin "2") (pinfunction "2_2") (pintype "passive"))
      (node (ref "L5") (pin "1") (pinfunction "1_1") (pintype "passive"))
    )
    (net (code "33") (name "Net-(C45-Pad2)") (class "Default")
      (node (ref "C45") (pin "2") (pinfunction "2_2") (pintype "passive"))
      (node (ref "L6") (pin "2") (pinfunction "2_2") (pintype "passive"))
    )
    (net (code "34") (name "Net-(U7-OutA)") (class "Default")
      (node (ref "C23") (pin "2") (pinfunction "2_2") (pintype "passive"))
      (node (ref "R10") (pin "2") (pinfunction "2_2") (pintype "passive"))
      (node (ref "R13") (pin "1") (pinfunction "1_1") (pintype "passive"))
      (node (ref "U7") (pin "1") (pinfunction "OutA_1") (pintype "passive"))
    )
    (net (code "35") (name "Net-(U7-OutB)") (class "Default")
      (node (ref "C27") (pin "2") (pinfunction "2_2") (pintype "passive"))
      (node (ref "R16") (pin "2") (pinfunction "2_2") (pintype "passive"))
      (node (ref "R18") (pin "2") (pinfunction "2_2") (pintype "passive"))
      (node (ref "U7") (pin "7") (pinfunction "OutB_7") (pintype "passive"))
    )
    (net (code "36") (name "Net-(U7-OutC)") (class "Default")
      (node (ref "C28") (pin "1") (pinfunction "1_1") (pintype "passive"))
      (node (ref "R17") (pin "2") (pinfunction "2_2") (pintype "passive"))
      (node (ref "R19") (pin "1") (pinfunction "1_1") (pintype "passive"))
      (node (ref "U7") (pin "8") (pinfunction "OutC_8") (pintype "passive"))
    )
    (net (code "37") (name "Net-(U7-OutD)") (class "Default")
      (node (ref "C24") (pin "1") (pinfunction "1_1") (pintype "passive"))
      (node (ref "R11") (pin "1") (pinfunction "1_1") (pintype "passive"))
      (node (ref "R14") (pin "1") (pinfunction "1_1") (pintype "passive"))
      (node (ref "U7") (pin "14") (pinfunction "OutD_14") (pintype "passive"))
    )
    (net (code "38") (name "Net-(U8-+Sense)") (class "Default")
      (node (ref "C29") (pin "1") (pinfunction "1_1") (pintype "passive"))
      (node (ref "R21") (pin "2") (pinfunction "2_2") (pintype "passive"))
      (node (ref "U8") (pin "13") (pinfunction "+Sense_13") (pintype "passive"))
      (node (ref "U8") (pin "14") (pinfunction "+VO_14") (pintype "passive"))
    )
    (net (code "39") (name "Net-(U8-VIN)") (class "Default")
      (node (ref "C40") (pin "2") (pinfunction "2_2") (pintype "passive"))
      (node (ref "R23") (pin "2") (pinfunction "2_2") (pintype "passive"))
      (node (ref "U8") (pin "6") (pinfunction "VIN_6") (pintype "passive"))
    )
    (net (code "40") (name "Net-(U8-–Sense)") (class "Default")
      (node (ref "C30") (pin "1") (pinfunction "1_1") (pintype "passive"))
      (node (ref "R20") (pin "1") (pinfunction "1_1") (pintype "passive"))
      (node (ref "U8") (pin "3") (pinfunction "–VO_3") (pintype "passive"))
      (node (ref "U8") (pin "4") (pinfunction "–Sense_4") (pintype "passive"))
    )
    (net (code "41") (name "Net-(U9-LIN+)") (class "Default")
      (node (ref "R26") (pin "2") (pinfunction "2_2") (pintype "passive"))
      (node (ref "R30") (pin "2") (pinfunction "2_2") (pintype "passive"))
      (node (ref "U9") (pin "4") (pinfunction "LIN+_4") (pintype "passive"))
    )
    (net (code "42") (name "Net-(U9-LIN-)") (class "Default")
      (node (ref "R28") (pin "2") (pinfunction "2_2") (pintype "passive"))
      (node (ref "R32") (pin "2") (pinfunction "2_2") (pintype "passive"))
      (node (ref "U9") (pin "5") (pinfunction "LIN-_5") (pintype "passive"))
    )
    (net (code "43") (name "Net-(U9-RIN+)") (class "Default")
      (node (ref "R27") (pin "2") (pinfunction "2_2") (pintype "passive"))
      (node (ref "R31") (pin "2") (pinfunction "2_2") (pintype "passive"))
      (node (ref "U9") (pin "17") (pinfunction "RIN+_17") (pintype "passive"))
    )
    (net (code "44") (name "Net-(U9-RIN-)") (class "Default")
      (node (ref "R29") (pin "2") (pinfunction "2_2") (pintype "passive"))
      (node (ref "R33") (pin "2") (pinfunction "2_2") (pintype "passive"))
      (node (ref "U9") (pin "16") (pinfunction "RIN-_16") (pintype "passive"))
    )
    (net (code "45") (name "Net-(U10-+Sense)") (class "Default")
      (node (ref "C45") (pin "1") (pinfunction "1_1") (pintype "passive"))
      (node (ref "R35") (pin "2") (pinfunction "2_2") (pintype "passive"))
      (node (ref "U10") (pin "13") (pinfunction "+Sense_13") (pintype "passive"))
      (node (ref "U10") (pin "14") (pinfunction "+VO_14") (pintype "passive"))
    )
    (net (code "46") (name "Net-(U10-VIN)") (class "Default")
      (node (ref "C47") (pin "2") (pinfunction "2_2") (pintype "passive"))
      (node (ref "R37") (pin "2") (pinfunction "2_2") (pintype "passive"))
      (node (ref "U10") (pin "6") (pinfunction "VIN_6") (pintype "passive"))
    )
    (net (code "47") (name "Net-(U10-–Sense)") (class "Default")
      (node (ref "C44") (pin "1") (pinfunction "1_1") (pintype "passive"))
      (node (ref "R34") (pin "1") (pinfunction "1_1") (pintype "passive"))
      (node (ref "U10") (pin "3") (pinfunction "–VO_3") (pintype "passive"))
      (node (ref "U10") (pin "4") (pinfunction "–Sense_4") (pintype "passive"))
    )
    (net (code "48") (name "unconnected-(U8-NC-Pad1)") (class "Default")
      (node (ref "U8") (pin "1") (pinfunction "NC_1") (pintype "passive"))
    )
    (net (code "49") (name "unconnected-(U8-NC-Pad2)") (class "Default")
      (node (ref "U8") (pin "2") (pinfunction "NC_2") (pintype "passive"))
    )
    (net (code "50") (name "unconnected-(U8-NC-Pad7)") (class "Default")
      (node (ref "U8") (pin "7") (pinfunction "NC_7") (pintype "passive"))
    )
    (net (code "51") (name "unconnected-(U8-NC-Pad8)") (class "Default")
      (node (ref "U8") (pin "8") (pinfunction "NC_8") (pintype "passive"))
    )
    (net (code "52") (name "unconnected-(U8-NC-Pad9)") (class "Default")
      (node (ref "U8") (pin "9") (pinfunction "NC_9") (pintype "passive"))
    )
    (net (code "53") (name "unconnected-(U8-NC-Pad10)") (class "Default")
      (node (ref "U8") (pin "10") (pinfunction "NC_10") (pintype "passive"))
    )
    (net (code "54") (name "unconnected-(U8-NC-Pad15)") (class "Default")
      (node (ref "U8") (pin "15") (pinfunction "NC_15") (pintype "passive"))
    )
    (net (code "55") (name "unconnected-(U8-NC-Pad16)") (class "Default")
      (node (ref "U8") (pin "16") (pinfunction "NC_16") (pintype "passive"))
    )
    (net (code "56") (name "unconnected-(U9-NC-Pad6)") (class "Default")
      (node (ref "U9") (pin "6") (pinfunction "NC_6") (pintype "passive"))
    )
    (net (code "57") (name "unconnected-(U9-NC-Pad7)") (class "Default")
      (node (ref "U9") (pin "7") (pinfunction "NC_7") (pintype "passive"))
    )
    (net (code "58") (name "unconnected-(U9-NC-Pad8)") (class "Default")
      (node (ref "U9") (pin "8") (pinfunction "NC_8") (pintype "passive"))
    )
    (net (code "59") (name "unconnected-(U9-NC-Pad9)") (class "Default")
      (node (ref "U9") (pin "9") (pinfunction "NC_9") (pintype "passive"))
    )
    (net (code "60") (name "unconnected-(U9-NC-Pad10)") (class "Default")
      (node (ref "U9") (pin "10") (pinfunction "NC_10") (pintype "passive"))
    )
    (net (code "61") (name "unconnected-(U9-NC-Pad11)") (class "Default")
      (node (ref "U9") (pin "11") (pinfunction "NC_11") (pintype "passive"))
    )
    (net (code "62") (name "unconnected-(U9-NC-Pad12)") (class "Default")
      (node (ref "U9") (pin "12") (pinfunction "NC_12") (pintype "passive"))
    )
    (net (code "63") (name "unconnected-(U9-NC-Pad13)") (class "Default")
      (node (ref "U9") (pin "13") (pinfunction "NC_13") (pintype "passive"))
    )
    (net (code "64") (name "unconnected-(U9-NC-Pad14)") (class "Default")
      (node (ref "U9") (pin "14") (pinfunction "NC_14") (pintype "passive"))
    )
    (net (code "65") (name "unconnected-(U9-NC-Pad15)") (class "Default")
      (node (ref "U9") (pin "15") (pinfunction "NC_15") (pintype "passive"))
    )
    (net (code "66") (name "unconnected-(U10-NC-Pad1)") (class "Default")
      (node (ref "U10") (pin "1") (pinfunction "NC_1") (pintype "passive"))
    )
    (net (code "67") (name "unconnected-(U10-NC-Pad2)") (class "Default")
      (node (ref "U10") (pin "2") (pinfunction "NC_2") (pintype "passive"))
    )
    (net (code "68") (name "unconnected-(U10-NC-Pad7)") (class "Default")
      (node (ref "U10") (pin "7") (pinfunction "NC_7") (pintype "passive"))
    )
    (net (code "69") (name "unconnected-(U10-NC-Pad8)") (class "Default")
      (node (ref "U10") (pin "8") (pinfunction "NC_8") (pintype "passive"))
    )
    (net (code "70") (name "unconnected-(U10-NC-Pad9)") (class "Default")
      (node (ref "U10") (pin "9") (pinfunction "NC_9") (pintype "passive"))
    )
    (net (code "71") (name "unconnected-(U10-NC-Pad10)") (class "Default")
      (node (ref "U10") (pin "10") (pinfunction "NC_10") (pintype "passive"))
    )
    (net (code "72") (name "unconnected-(U10-NC-Pad15)") (class "Default")
      (node (ref "U10") (pin "15") (pinfunction "NC_15") (pintype "passive"))
    )
    (net (code "73") (name "unconnected-(U10-NC-Pad16)") (class "Default")
      (node (ref "U10") (pin "16") (pinfunction "NC_16") (pintype "passive"))
    )
  )
)
